# Sch_Buck.net
KiCad netlist of a schematic drawn in Altium Designer
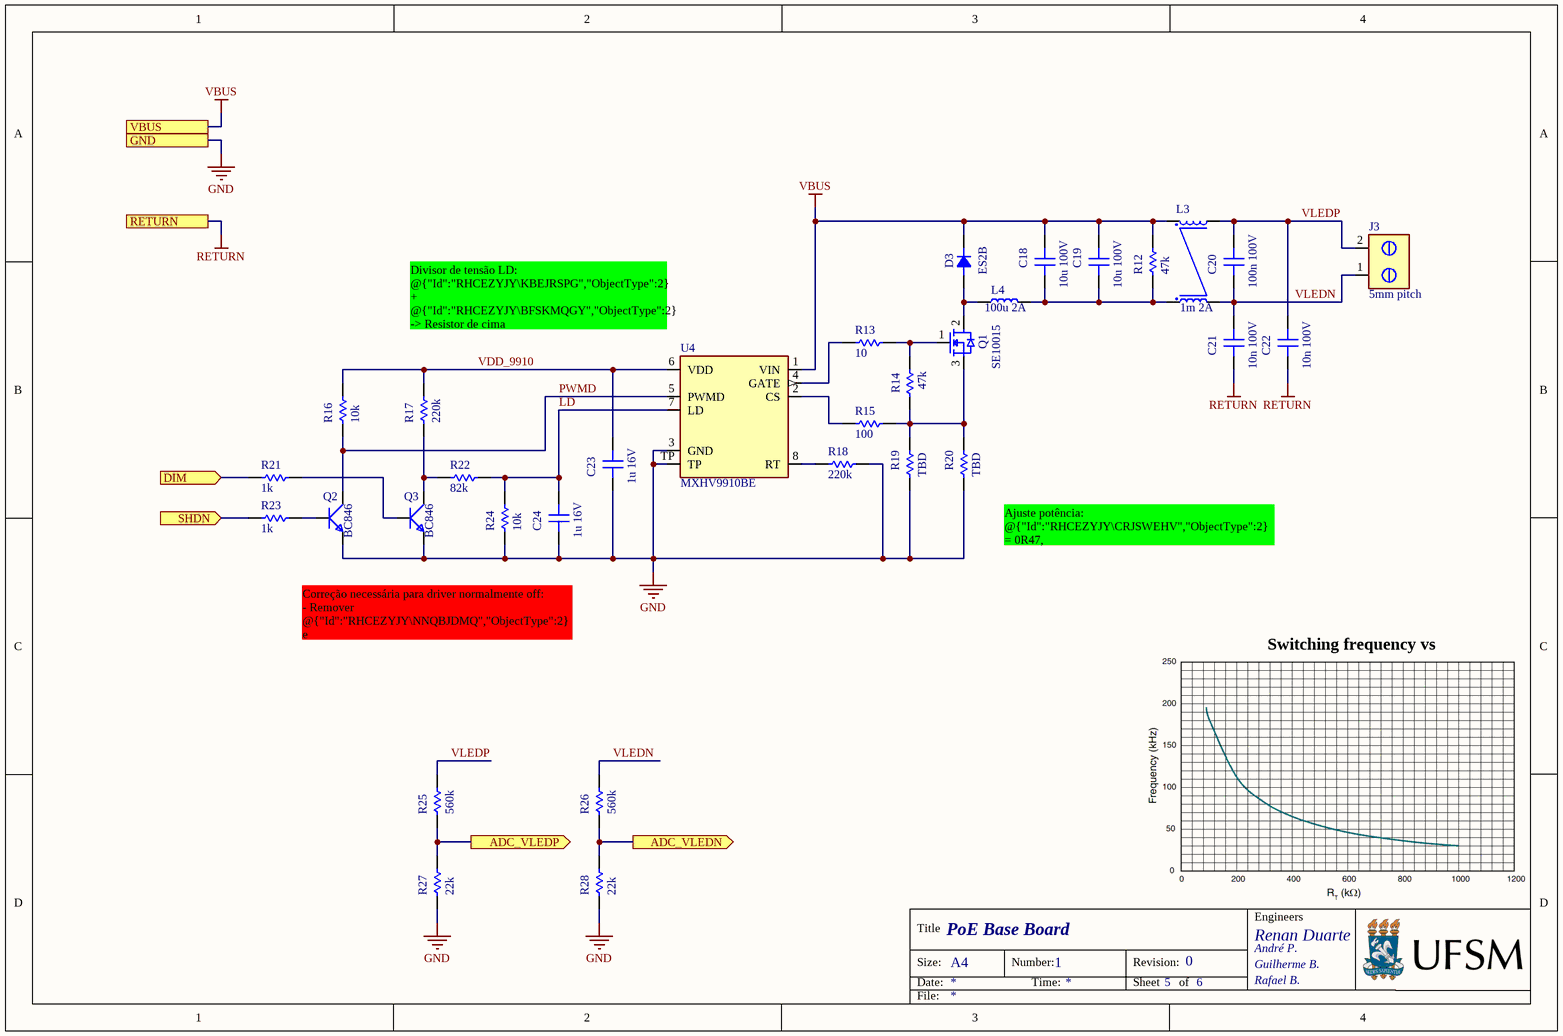
[diagram p0: Sch_Buck.SchDoc]

(export (version "E")
  (design (tool "Eeschema 10.0.6"))
  (components
    (comp (ref "C18")
      (value "10u 100V")
      (footprint "CAP_SMD_1210")
      (description "Capacitor SMD - Generic")
      (libsource (lib "AltiumLibrary") (part "CAP_SMD"))
    )
    (comp (ref "C19")
      (value "10u 100V")
      (footprint "CAP_SMD_1210")
      (description "Capacitor SMD - Generic")
      (libsource (lib "AltiumLibrary") (part "CAP_SMD"))
    )
    (comp (ref "C20")
      (value "100n 100V")
      (footprint "CAP_SMD_1206")
      (description "Capacitor SMD - Generic")
      (libsource (lib "AltiumLibrary") (part "CAP_SMD"))
    )
    (comp (ref "C21")
      (value "10n 100V")
      (footprint "CAP_SMD_0603")
      (description "Capacitor SMD - Generic")
      (libsource (lib "AltiumLibrary") (part "CAP_SMD"))
    )
    (comp (ref "C22")
      (value "10n 100V")
      (footprint "CAP_SMD_0603")
      (description "Capacitor SMD - Generic")
      (libsource (lib "AltiumLibrary") (part "CAP_SMD"))
    )
    (comp (ref "C23")
      (value "1u 16V")
      (footprint "CAP_SMD_0603")
      (description "Capacitor SMD - Generic")
      (libsource (lib "AltiumLibrary") (part "CAP_SMD"))
    )
    (comp (ref "C24")
      (value "1u 16V")
      (footprint "CAP_SMD_0603")
      (description "Capacitor SMD - Generic")
      (libsource (lib "AltiumLibrary") (part "CAP_SMD"))
    )
    (comp (ref "D3")
      (value "ES2B")
      (footprint "D_SMA")
      (description "100V 2A Super Fast Recovery Rectifier")
      (libsource (lib "AltiumLibrary") (part "ES1J"))
    )
    (comp (ref "J3")
      (value "5mm pitch")
      (footprint "CON_SCREW_5mm")
      (description "5mm pitch 2P screw terminal block")
      (libsource (lib "AltiumLibrary") (part "CON_SCREW-2P-5mm"))
    )
    (comp (ref "L3")
      (value "1m 2A")
      (footprint "IND_CM_PTH_10x6x5")
      (description "Common mode inductor PTH- Generic")
      (libsource (lib "AltiumLibrary") (part "IND_CM_PTH"))
    )
    (comp (ref "L4")
      (value "100u 2A")
      (footprint "IND_SMD7.1x6.6x5")
      (description "Inductor SMD - Generic")
      (libsource (lib "AltiumLibrary") (part "IND_SMD"))
    )
    (comp (ref "Q1")
      (value "SE10015")
      (footprint "IC_TO252")
      (description "100V 15A 80mOhm N MOSFET")
      (libsource (lib "AltiumLibrary") (part "MOSFET_SMD"))
    )
    (comp (ref "Q2")
      (value "BC846")
      (footprint "IC_SOT23")
      (description "SMD transistor NPN - Generic")
      (libsource (lib "AltiumLibrary") (part "TRAN_SMD_NPN"))
    )
    (comp (ref "Q3")
      (value "BC846")
      (footprint "IC_SOT23")
      (description "SMD transistor NPN - Generic")
      (libsource (lib "AltiumLibrary") (part "TRAN_SMD_NPN"))
    )
    (comp (ref "R12")
      (value "47k")
      (footprint "RES_SMD_1206")
      (description "Resistor SMD - Generic")
      (libsource (lib "AltiumLibrary") (part "RES_SMD"))
    )
    (comp (ref "R13")
      (value "10")
      (footprint "RES_SMD_0603")
      (description "Resistor SMD - Generic")
      (libsource (lib "") (part "RES_SMD_1"))
    )
    (comp (ref "R14")
      (value "47k")
      (footprint "RES_SMD_0603")
      (description "Resistor SMD - Generic")
      (libsource (lib "") (part "RES_SMD_1"))
    )
    (comp (ref "R15")
      (value "100")
      (footprint "RES_SMD_0603")
      (description "Resistor SMD - Generic")
      (libsource (lib "") (part "RES_SMD_1"))
    )
    (comp (ref "R16")
      (value "10k")
      (footprint "RES_SMD_0603")
      (description "Resistor SMD - Generic")
      (libsource (lib "AltiumLibrary") (part "RES_SMD"))
    )
    (comp (ref "R17")
      (value "220k")
      (footprint "RES_SMD_0603")
      (description "Resistor SMD - Generic")
      (libsource (lib "AltiumLibrary") (part "RES_SMD"))
    )
    (comp (ref "R18")
      (value "220k")
      (footprint "RES_SMD_0603")
      (description "Resistor SMD - Generic")
      (libsource (lib "AltiumLibrary") (part "RES_SMD"))
    )
    (comp (ref "R19")
      (value "TBD")
      (footprint "RES_SMD_1206")
      (description "Resistor SMD - Generic")
      (libsource (lib "AltiumLibrary") (part "RES_SMD"))
    )
    (comp (ref "R20")
      (value "TBD")
      (footprint "RES_SMD_1206")
      (description "Resistor SMD - Generic")
      (libsource (lib "AltiumLibrary") (part "RES_SMD"))
    )
    (comp (ref "R21")
      (value "1k")
      (footprint "RES_SMD_0603")
      (description "Resistor SMD - Generic")
      (libsource (lib "AltiumLibrary") (part "RES_SMD"))
    )
    (comp (ref "R22")
      (value "82k")
      (footprint "RES_SMD_0603")
      (description "Resistor SMD - Generic")
      (libsource (lib "") (part "RES_SMD_1"))
    )
    (comp (ref "R23")
      (value "1k")
      (footprint "RES_SMD_0603")
      (description "Resistor SMD - Generic")
      (libsource (lib "AltiumLibrary") (part "RES_SMD"))
    )
    (comp (ref "R24")
      (value "10k")
      (footprint "RES_SMD_0603")
      (description "Resistor SMD - Generic")
      (libsource (lib "AltiumLibrary") (part "RES_SMD"))
    )
    (comp (ref "R25")
      (value "560k")
      (footprint "RES_SMD_0603")
      (description "Resistor SMD - Generic")
      (libsource (lib "AltiumLibrary") (part "RES_SMD"))
    )
    (comp (ref "R26")
      (value "560k")
      (footprint "RES_SMD_0603")
      (description "Resistor SMD - Generic")
      (libsource (lib "AltiumLibrary") (part "RES_SMD"))
    )
    (comp (ref "R27")
      (value "22k")
      (footprint "RES_SMD_0603")
      (description "Resistor SMD - Generic")
      (libsource (lib "AltiumLibrary") (part "RES_SMD"))
    )
    (comp (ref "R28")
      (value "22k")
      (footprint "RES_SMD_0603")
      (description "Resistor SMD - Generic")
      (libsource (lib "AltiumLibrary") (part "RES_SMD"))
    )
    (comp (ref "U4")
      (value "MXHV9910BE")
      (footprint "IC_SOIC8_TP")
      (description "Off-Line, High Brightness LED Driver")
      (libsource (lib "AltiumLibrary") (part "MXHV9910BE"))
    )
  )
  (nets
    (net (code "1") (name "/ADC_VLEDN") (class "Default")
      (node (ref "R26") (pin "2") (pinfunction "2_2") (pintype "passive"))
      (node (ref "R28") (pin "1") (pinfunction "1_1") (pintype "passive"))
    )
    (net (code "2") (name "/ADC_VLEDP") (class "Default")
      (node (ref "R25") (pin "2") (pinfunction "2_2") (pintype "passive"))
      (node (ref "R27") (pin "1") (pinfunction "1_1") (pintype "passive"))
    )
    (net (code "3") (name "/DIM") (class "Default")
      (node (ref "R21") (pin "2") (pinfunction "2_2") (pintype "passive"))
    )
    (net (code "4") (name "/LD") (class "Default")
      (node (ref "C24") (pin "1") (pinfunction "1_1") (pintype "passive"))
      (node (ref "R22") (pin "2") (pinfunction "2_2") (pintype "passive"))
      (node (ref "R24") (pin "1") (pinfunction "1_1") (pintype "passive"))
      (node (ref "U4") (pin "7") (pinfunction "LD_7") (pintype "passive"))
    )
    (net (code "5") (name "/PWMD") (class "Default")
      (node (ref "Q2") (pin "3") (pinfunction "C_3") (pintype "passive"))
      (node (ref "R16") (pin "2") (pinfunction "2_2") (pintype "passive"))
      (node (ref "U4") (pin "5") (pinfunction "PWMD_5") (pintype "passive"))
    )
    (net (code "6") (name "/SHDN") (class "Default")
      (node (ref "R23") (pin "2") (pinfunction "2_2") (pintype "passive"))
    )
    (net (code "7") (name "/VDD_9910") (class "Default")
      (node (ref "C23") (pin "1") (pinfunction "1_1") (pintype "passive"))
      (node (ref "R16") (pin "1") (pinfunction "1_1") (pintype "passive"))
      (node (ref "R17") (pin "1") (pinfunction "1_1") (pintype "passive"))
      (node (ref "U4") (pin "6") (pinfunction "VDD_6") (pintype "power_in"))
    )
    (net (code "8") (name "/VLEDN") (class "Default")
      (node (ref "C20") (pin "2") (pinfunction "2_2") (pintype "passive"))
      (node (ref "C21") (pin "1") (pinfunction "1_1") (pintype "passive"))
      (node (ref "J3") (pin "1") (pinfunction "1_1") (pintype "passive"))
      (node (ref "L3") (pin "2") (pinfunction "2_2") (pintype "passive"))
      (node (ref "R26") (pin "1") (pinfunction "1_1") (pintype "passive"))
    )
    (net (code "9") (name "/VLEDP") (class "Default")
      (node (ref "C20") (pin "1") (pinfunction "1_1") (pintype "passive"))
      (node (ref "C22") (pin "1") (pinfunction "1_1") (pintype "passive"))
      (node (ref "J3") (pin "2") (pinfunction "2_2") (pintype "passive"))
      (node (ref "L3") (pin "4") (pinfunction "4_4") (pintype "passive"))
      (node (ref "R25") (pin "1") (pinfunction "1_1") (pintype "passive"))
    )
    (net (code "10") (name "GND") (class "Default")
      (node (ref "C23") (pin "2") (pinfunction "2_2") (pintype "passive"))
      (node (ref "C24") (pin "2") (pinfunction "2_2") (pintype "passive"))
      (node (ref "Q2") (pin "2") (pinfunction "E_2") (pintype "passive"))
      (node (ref "Q3") (pin "2") (pinfunction "E_2") (pintype "passive"))
      (node (ref "R18") (pin "1") (pinfunction "1_1") (pintype "passive"))
      (node (ref "R19") (pin "2") (pinfunction "2_2") (pintype "passive"))
      (node (ref "R20") (pin "2") (pinfunction "2_2") (pintype "passive"))
      (node (ref "R24") (pin "2") (pinfunction "2_2") (pintype "passive"))
      (node (ref "R27") (pin "2") (pinfunction "2_2") (pintype "passive"))
      (node (ref "R28") (pin "2") (pinfunction "2_2") (pintype "passive"))
      (node (ref "U4") (pin "3") (pinfunction "GND_3") (pintype "power_in"))
      (node (ref "U4") (pin "TP") (pinfunction "TP_TP") (pintype "power_in"))
    )
    (net (code "11") (name "Net-(C18-Pad2)") (class "Default")
      (node (ref "C18") (pin "2") (pinfunction "2_2") (pintype "passive"))
      (node (ref "C19") (pin "2") (pinfunction "2_2") (pintype "passive"))
      (node (ref "L3") (pin "1") (pinfunction "1_1") (pintype "passive"))
      (node (ref "L4") (pin "2") (pinfunction "2_2") (pintype "passive"))
      (node (ref "R12") (pin "2") (pinfunction "2_2") (pintype "passive"))
    )
    (net (code "12") (name "Net-(Q1-D1)") (class "Default")
      (node (ref "D3") (pin "A") (pinfunction "A_A") (pintype "passive"))
      (node (ref "L4") (pin "1") (pinfunction "1_1") (pintype "passive"))
      (node (ref "Q1") (pin "2") (pinfunction "D1_2") (pintype "passive"))
    )
    (net (code "13") (name "Net-(Q1-G1)") (class "Default")
      (node (ref "Q1") (pin "1") (pinfunction "G1_1") (pintype "passive"))
      (node (ref "R13") (pin "2") (pinfunction "2_2") (pintype "passive"))
      (node (ref "R14") (pin "2") (pinfunction "2_2") (pintype "passive"))
    )
    (net (code "14") (name "Net-(Q1-S1)") (class "Default")
      (node (ref "Q1") (pin "3") (pinfunction "S1_3") (pintype "passive"))
      (node (ref "R14") (pin "1") (pinfunction "1_1") (pintype "passive"))
      (node (ref "R15") (pin "2") (pinfunction "2_2") (pintype "passive"))
      (node (ref "R19") (pin "1") (pinfunction "1_1") (pintype "passive"))
      (node (ref "R20") (pin "1") (pinfunction "1_1") (pintype "passive"))
    )
    (net (code "15") (name "Net-(Q2-B)") (class "Default")
      (node (ref "Q2") (pin "1") (pinfunction "B_1") (pintype "passive"))
      (node (ref "R23") (pin "1") (pinfunction "1_1") (pintype "passive"))
    )
    (net (code "16") (name "Net-(Q3-B)") (class "Default")
      (node (ref "Q3") (pin "1") (pinfunction "B_1") (pintype "passive"))
      (node (ref "R21") (pin "1") (pinfunction "1_1") (pintype "passive"))
    )
    (net (code "17") (name "Net-(Q3-C)") (class "Default")
      (node (ref "Q3") (pin "3") (pinfunction "C_3") (pintype "passive"))
      (node (ref "R17") (pin "2") (pinfunction "2_2") (pintype "passive"))
      (node (ref "R22") (pin "1") (pinfunction "1_1") (pintype "passive"))
    )
    (net (code "18") (name "Net-(U4-CS)") (class "Default")
      (node (ref "R15") (pin "1") (pinfunction "1_1") (pintype "passive"))
      (node (ref "U4") (pin "2") (pinfunction "CS_2") (pintype "passive"))
    )
    (net (code "19") (name "Net-(U4-GATE)") (class "Default")
      (node (ref "R13") (pin "1") (pinfunction "1_1") (pintype "passive"))
      (node (ref "U4") (pin "4") (pinfunction "GATE_4") (pintype "output"))
    )
    (net (code "20") (name "Net-(U4-RT)") (class "Default")
      (node (ref "R18") (pin "2") (pinfunction "2_2") (pintype "passive"))
      (node (ref "U4") (pin "8") (pinfunction "RT_8") (pintype "passive"))
    )
    (net (code "21") (name "RETURN") (class "Default")
      (node (ref "C21") (pin "2") (pinfunction "2_2") (pintype "passive"))
      (node (ref "C22") (pin "2") (pinfunction "2_2") (pintype "passive"))
    )
    (net (code "22") (name "VBUS") (class "Default")
      (node (ref "C18") (pin "1") (pinfunction "1_1") (pintype "passive"))
      (node (ref "C19") (pin "1") (pinfunction "1_1") (pintype "passive"))
      (node (ref "D3") (pin "K") (pinfunction "K_K") (pintype "passive"))
      (node (ref "L3") (pin "3") (pinfunction "3_3") (pintype "passive"))
      (node (ref "R12") (pin "1") (pinfunction "1_1") (pintype "passive"))
      (node (ref "U4") (pin "1") (pinfunction "VIN_1") (pintype "power_in"))
    )
  )
)
